# PDD.net
KiCad netlist of a schematic drawn in EAGLE
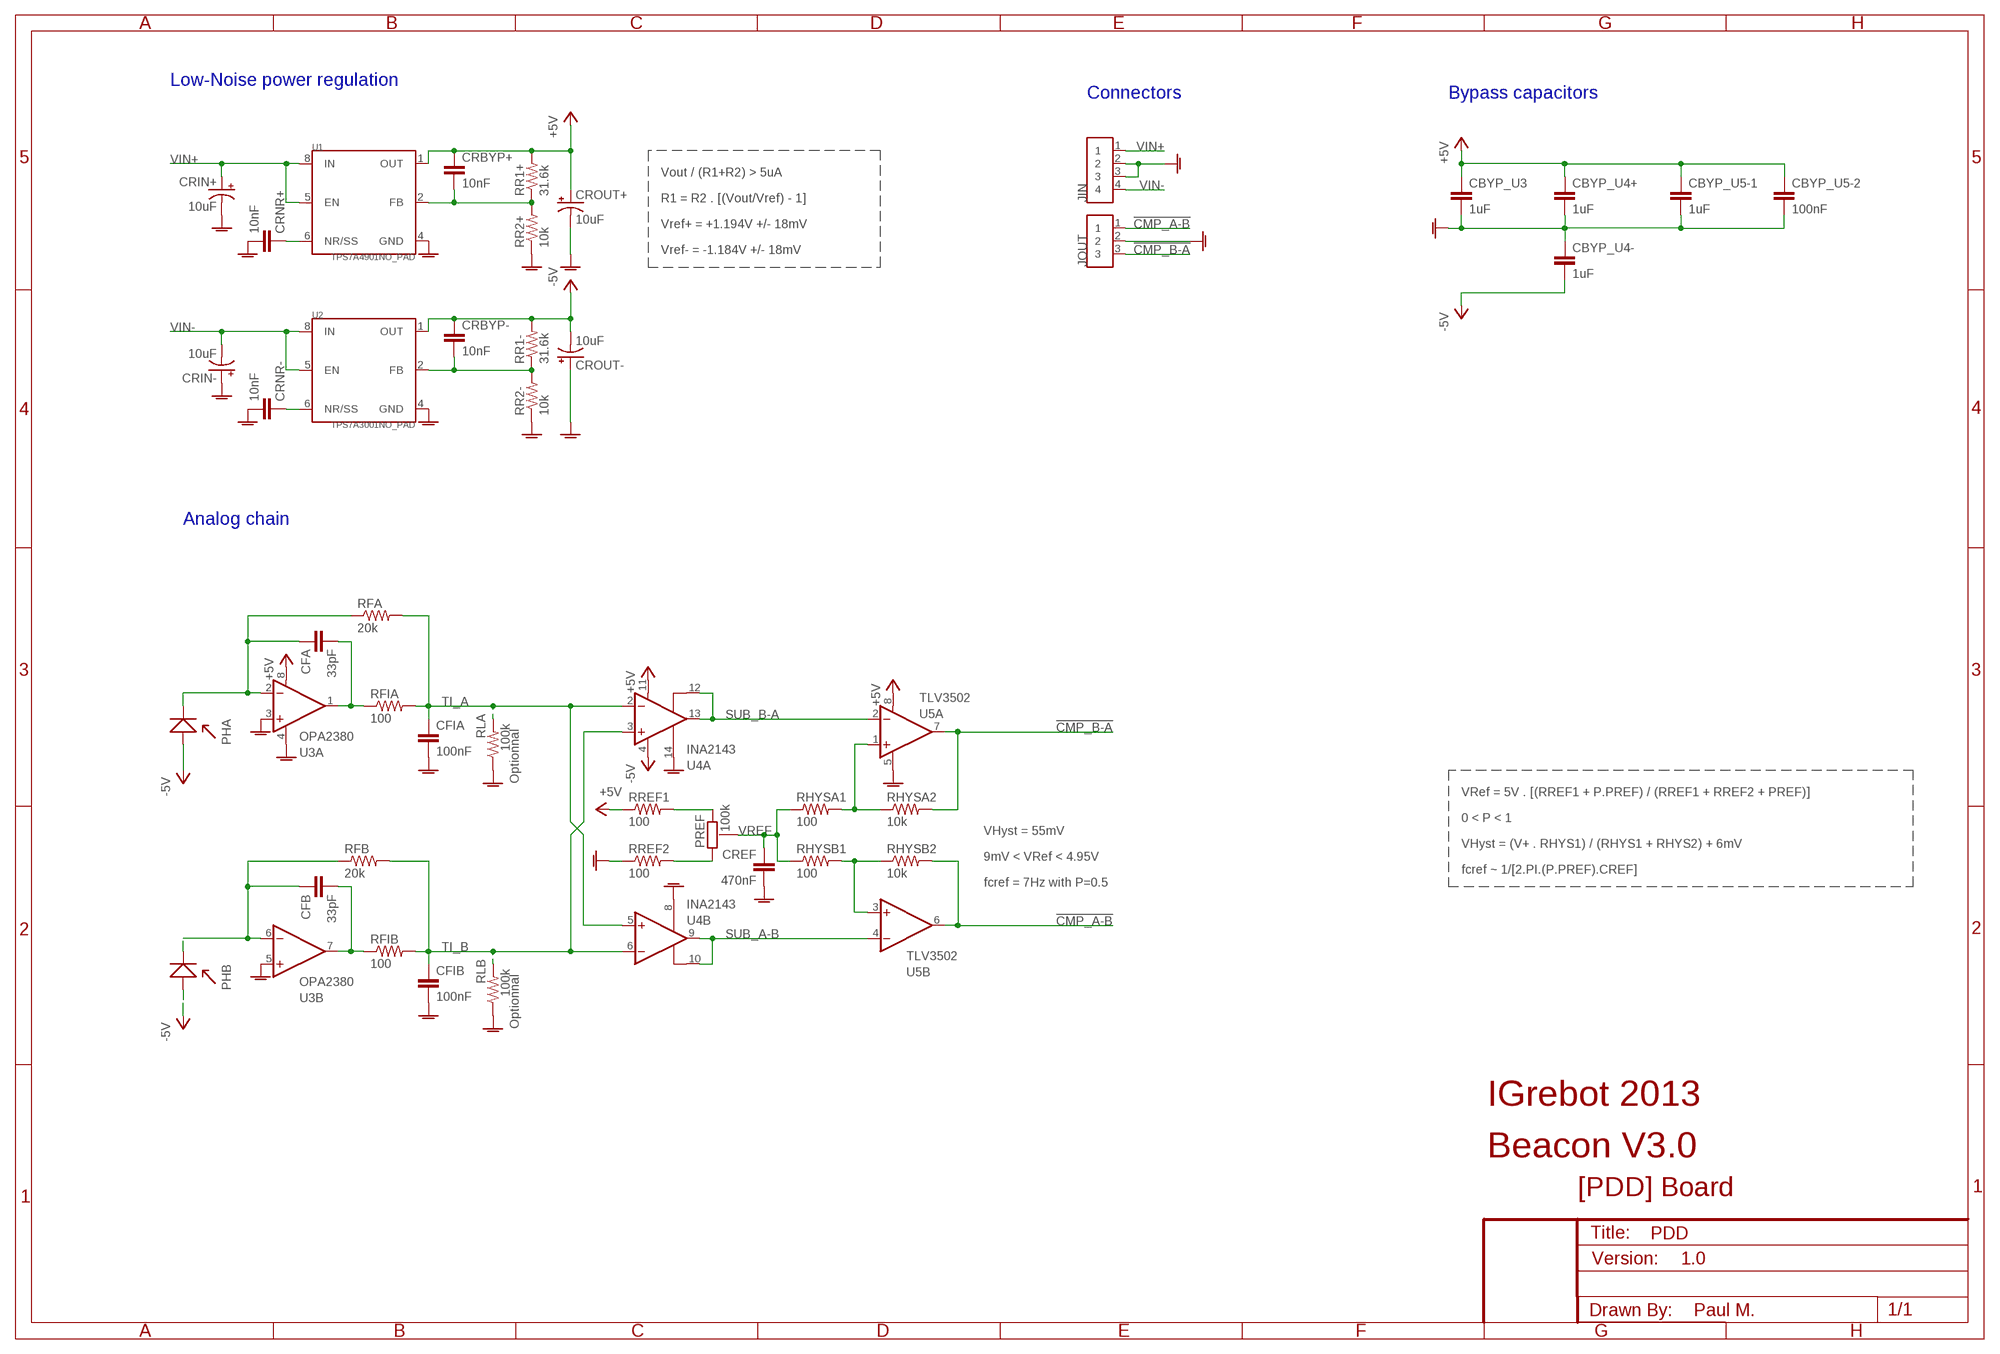
[diagram p0: schematic, sheet 1]

(export (version "E")
  (design (tool "Eeschema 10.0.6"))
  (components
    (comp (ref "CBYP_U3")
      (value "1uF")
      (footprint "eagle-import:0603-CAP")
      (libsource (lib "eagle-import") (part "CAP0603-CAP"))
    )
    (comp (ref "CBYP_U4+")
      (value "1uF")
      (footprint "eagle-import:0603-CAP")
      (libsource (lib "eagle-import") (part "CAP0603-CAP"))
    )
    (comp (ref "CBYP_U4-")
      (value "1uF")
      (footprint "eagle-import:0603-CAP")
      (libsource (lib "eagle-import") (part "CAP0603-CAP"))
    )
    (comp (ref "CBYP_U5-1")
      (value "1uF")
      (footprint "eagle-import:0603-CAP")
      (libsource (lib "eagle-import") (part "CAP0603-CAP"))
    )
    (comp (ref "CBYP_U5-2")
      (value "100nF")
      (footprint "eagle-import:0603-CAP")
      (libsource (lib "eagle-import") (part "CAP0603-CAP"))
    )
    (comp (ref "CFA")
      (value "33pF")
      (footprint "eagle-import:0603-CAP")
      (libsource (lib "eagle-import") (part "CAP0603-CAP"))
    )
    (comp (ref "CFB")
      (value "33pF")
      (footprint "eagle-import:0603-CAP")
      (libsource (lib "eagle-import") (part "CAP0603-CAP"))
    )
    (comp (ref "CFIA")
      (value "100nF")
      (footprint "eagle-import:0603-CAP")
      (libsource (lib "eagle-import") (part "CAP0603-CAP"))
    )
    (comp (ref "CFIB")
      (value "100nF")
      (footprint "eagle-import:0603-CAP")
      (libsource (lib "eagle-import") (part "CAP0603-CAP"))
    )
    (comp (ref "CRBYP+")
      (value "10nF")
      (footprint "eagle-import:0603-CAP")
      (libsource (lib "eagle-import") (part "CAP0603-CAP"))
    )
    (comp (ref "CRBYP-")
      (value "10nF")
      (footprint "eagle-import:0603-CAP")
      (libsource (lib "eagle-import") (part "CAP0603-CAP"))
    )
    (comp (ref "CREF")
      (value "470nF")
      (footprint "eagle-import:0603-CAP")
      (libsource (lib "eagle-import") (part "CAP0603-CAP"))
    )
    (comp (ref "CRIN+")
      (value "10uF")
      (footprint "eagle-import:EIA3528-KIT")
      (libsource (lib "eagle-import") (part "CAP_POL3528-KIT"))
    )
    (comp (ref "CRIN-")
      (value "10uF")
      (footprint "eagle-import:EIA3528-KIT")
      (libsource (lib "eagle-import") (part "CAP_POL3528-KIT"))
    )
    (comp (ref "CRNR+")
      (value "10nF")
      (footprint "eagle-import:0603-CAP")
      (libsource (lib "eagle-import") (part "CAP0603-CAP"))
    )
    (comp (ref "CRNR-")
      (value "10nF")
      (footprint "eagle-import:0603-CAP")
      (libsource (lib "eagle-import") (part "CAP0603-CAP"))
    )
    (comp (ref "CROUT+")
      (value "10uF")
      (footprint "eagle-import:EIA3528-KIT")
      (libsource (lib "eagle-import") (part "CAP_POL3528-KIT"))
    )
    (comp (ref "CROUT-")
      (value "10uF")
      (footprint "eagle-import:EIA3528-KIT")
      (libsource (lib "eagle-import") (part "CAP_POL3528-KIT"))
    )
    (comp (ref "JIN")
      (value "SIL4")
      (footprint "eagle-import:CON4-2.54")
      (libsource (lib "eagle-import") (part "SIL4"))
    )
    (comp (ref "JOUT")
      (value "SIL3")
      (footprint "eagle-import:CON3-2.54")
      (libsource (lib "eagle-import") (part "SIL3"))
    )
    (comp (ref "PHA")
      (value "VBPW34SR")
      (footprint "eagle-import:VBPW34SR")
      (libsource (lib "eagle-import") (part "VBPW34SR"))
    )
    (comp (ref "PHB")
      (value "VBPW34SR")
      (footprint "eagle-import:VBPW34SR")
      (libsource (lib "eagle-import") (part "VBPW34SR"))
    )
    (comp (ref "PREF")
      (value "100k")
      (footprint "eagle-import:TRIM-PVZ2A")
      (libsource (lib "eagle-import") (part "PVZ2A"))
    )
    (comp (ref "RFA")
      (value "20k")
      (footprint "eagle-import:0603-RES")
      (libsource (lib "eagle-import") (part "RESISTOR0603-RES"))
    )
    (comp (ref "RFB")
      (value "20k")
      (footprint "eagle-import:0603-RES")
      (libsource (lib "eagle-import") (part "RESISTOR0603-RES"))
    )
    (comp (ref "RFIA")
      (value "100")
      (footprint "eagle-import:0603-RES")
      (libsource (lib "eagle-import") (part "RESISTOR0603-RES"))
    )
    (comp (ref "RFIB")
      (value "100")
      (footprint "eagle-import:0603-RES")
      (libsource (lib "eagle-import") (part "RESISTOR0603-RES"))
    )
    (comp (ref "RHYSA1")
      (value "100")
      (footprint "eagle-import:0603-RES")
      (libsource (lib "eagle-import") (part "RESISTOR0603-RES"))
    )
    (comp (ref "RHYSA2")
      (value "10k")
      (footprint "eagle-import:0603-RES")
      (libsource (lib "eagle-import") (part "RESISTOR0603-RES"))
    )
    (comp (ref "RHYSB1")
      (value "100")
      (footprint "eagle-import:0603-RES")
      (libsource (lib "eagle-import") (part "RESISTOR0603-RES"))
    )
    (comp (ref "RHYSB2")
      (value "10k")
      (footprint "eagle-import:0603-RES")
      (libsource (lib "eagle-import") (part "RESISTOR0603-RES"))
    )
    (comp (ref "RLA")
      (value "100k")
      (footprint "eagle-import:0603-RES")
      (libsource (lib "eagle-import") (part "RESISTOR0603-RES"))
    )
    (comp (ref "RLB")
      (value "100k")
      (footprint "eagle-import:0603-RES")
      (libsource (lib "eagle-import") (part "RESISTOR0603-RES"))
    )
    (comp (ref "RR1+")
      (value "31.6k")
      (footprint "eagle-import:0603-RES")
      (libsource (lib "eagle-import") (part "RESISTOR0603-RES"))
    )
    (comp (ref "RR1-")
      (value "31.6k")
      (footprint "eagle-import:0603-RES")
      (libsource (lib "eagle-import") (part "RESISTOR0603-RES"))
    )
    (comp (ref "RR2+")
      (value "10k")
      (footprint "eagle-import:0603-RES")
      (libsource (lib "eagle-import") (part "RESISTOR0603-RES"))
    )
    (comp (ref "RR2-")
      (value "10k")
      (footprint "eagle-import:0603-RES")
      (libsource (lib "eagle-import") (part "RESISTOR0603-RES"))
    )
    (comp (ref "RREF1")
      (value "100")
      (footprint "eagle-import:0603-RES")
      (libsource (lib "eagle-import") (part "RESISTOR0603-RES"))
    )
    (comp (ref "RREF2")
      (value "100")
      (footprint "eagle-import:0603-RES")
      (libsource (lib "eagle-import") (part "RESISTOR0603-RES"))
    )
    (comp (ref "U1")
      (value "TPS7A4901NO_PAD")
      (footprint "eagle-import:MSOP8")
      (libsource (lib "eagle-import") (part "TPS7A4901NO_PAD"))
    )
    (comp (ref "U2")
      (value "TPS7A3001NO_PAD")
      (footprint "eagle-import:MSOP8")
      (libsource (lib "eagle-import") (part "TPS7A3001NO_PAD"))
    )
    (comp (ref "U3")
      (value "OPA2380")
      (footprint "eagle-import:MSOP8")
      (libsource (lib "eagle-import") (part "OPA2380"))
    )
    (comp (ref "U4")
      (value "INA2143")
      (footprint "eagle-import:SOIC14")
      (libsource (lib "eagle-import") (part "INA2143"))
    )
    (comp (ref "U5")
      (value "TLV3502")
      (footprint "eagle-import:SOIC8")
      (libsource (lib "eagle-import") (part "TLV3502"))
    )
  )
  (nets
    (net (code "1") (name "+5V") (class "Default")
      (node (ref "CBYP_U3") (pin "1") (pinfunction "1_1") (pintype "passive"))
      (node (ref "CBYP_U4+") (pin "1") (pinfunction "1_1") (pintype "passive"))
      (node (ref "CBYP_U5-1") (pin "1") (pinfunction "1_1") (pintype "passive"))
      (node (ref "CBYP_U5-2") (pin "1") (pinfunction "1_1") (pintype "passive"))
      (node (ref "CRBYP+") (pin "1") (pinfunction "1_1") (pintype "passive"))
      (node (ref "CROUT+") (pin "A") (pinfunction "+_A") (pintype "passive"))
      (node (ref "RR1+") (pin "2") (pinfunction "2_2") (pintype "passive"))
      (node (ref "RREF1") (pin "1") (pinfunction "1_1") (pintype "passive"))
      (node (ref "U1") (pin "1") (pinfunction "OUT_1") (pintype "power_in"))
      (node (ref "U3") (pin "8") (pinfunction "V+_8") (pintype "power_in"))
      (node (ref "U4") (pin "11") (pinfunction "V+_11") (pintype "power_in"))
      (node (ref "U5") (pin "8") (pinfunction "V+_8") (pintype "power_in"))
    )
    (net (code "2") (name "-5V") (class "Default")
      (node (ref "CBYP_U4-") (pin "2") (pinfunction "2_2") (pintype "passive"))
      (node (ref "CRBYP-") (pin "1") (pinfunction "1_1") (pintype "passive"))
      (node (ref "CROUT-") (pin "C") (pinfunction "-_C") (pintype "passive"))
      (node (ref "PHA") (pin "A") (pinfunction "A_A") (pintype "bidirectional"))
      (node (ref "PHB") (pin "A") (pinfunction "A_A") (pintype "bidirectional"))
      (node (ref "RR1-") (pin "2") (pinfunction "2_2") (pintype "passive"))
      (node (ref "U2") (pin "1") (pinfunction "OUT_1") (pintype "power_in"))
      (node (ref "U4") (pin "4") (pinfunction "V-_4") (pintype "power_in"))
    )
    (net (code "3") (name "/SUB_A-B") (class "Default")
      (node (ref "U4") (pin "10") (pinfunction "SENSE_10") (pintype "bidirectional"))
      (node (ref "U4") (pin "9") (pinfunction "OUT_9") (pintype "output"))
      (node (ref "U5") (pin "4") (pinfunction "-IN_4") (pintype "input"))
    )
    (net (code "4") (name "/SUB_B-A") (class "Default")
      (node (ref "U4") (pin "12") (pinfunction "SENSE_12") (pintype "bidirectional"))
      (node (ref "U4") (pin "13") (pinfunction "OUT_13") (pintype "output"))
      (node (ref "U5") (pin "2") (pinfunction "-IN_2") (pintype "input"))
    )
    (net (code "5") (name "/TI_A") (class "Default")
      (node (ref "CFIA") (pin "1") (pinfunction "1_1") (pintype "passive"))
      (node (ref "RFA") (pin "2") (pinfunction "2_2") (pintype "passive"))
      (node (ref "RFIA") (pin "2") (pinfunction "2_2") (pintype "passive"))
      (node (ref "RLA") (pin "2") (pinfunction "2_2") (pintype "passive"))
      (node (ref "U4") (pin "2") (pinfunction "-IN_2") (pintype "input"))
      (node (ref "U4") (pin "5") (pinfunction "+IN_5") (pintype "input"))
    )
    (net (code "6") (name "/TI_B") (class "Default")
      (node (ref "CFIB") (pin "1") (pinfunction "1_1") (pintype "passive"))
      (node (ref "RFB") (pin "2") (pinfunction "2_2") (pintype "passive"))
      (node (ref "RFIB") (pin "2") (pinfunction "2_2") (pintype "passive"))
      (node (ref "RLB") (pin "2") (pinfunction "2_2") (pintype "passive"))
      (node (ref "U4") (pin "3") (pinfunction "+IN_3") (pintype "input"))
      (node (ref "U4") (pin "6") (pinfunction "-IN_6") (pintype "input"))
    )
    (net (code "7") (name "/VIN+") (class "Default")
      (node (ref "CRIN+") (pin "A") (pinfunction "+_A") (pintype "passive"))
      (node (ref "JIN") (pin "1") (pinfunction "1_1") (pintype "bidirectional"))
      (node (ref "U1") (pin "5") (pinfunction "EN_5") (pintype "input"))
      (node (ref "U1") (pin "8") (pinfunction "IN_8") (pintype "power_in"))
    )
    (net (code "8") (name "/VIN-") (class "Default")
      (node (ref "CRIN-") (pin "C") (pinfunction "-_C") (pintype "passive"))
      (node (ref "JIN") (pin "4") (pinfunction "4_4") (pintype "bidirectional"))
      (node (ref "U2") (pin "5") (pinfunction "EN_5") (pintype "input"))
      (node (ref "U2") (pin "8") (pinfunction "IN_8") (pintype "power_in"))
    )
    (net (code "9") (name "/VREF") (class "Default")
      (node (ref "CREF") (pin "1") (pinfunction "1_1") (pintype "passive"))
      (node (ref "PREF") (pin "2") (pinfunction "B_2") (pintype "bidirectional"))
      (node (ref "RHYSA1") (pin "1") (pinfunction "1_1") (pintype "passive"))
      (node (ref "RHYSB1") (pin "1") (pinfunction "1_1") (pintype "passive"))
    )
    (net (code "10") (name "/~{CMP_A-B}") (class "Default")
      (node (ref "JOUT") (pin "1") (pinfunction "1_1") (pintype "bidirectional"))
      (node (ref "RHYSB2") (pin "2") (pinfunction "2_2") (pintype "passive"))
      (node (ref "U5") (pin "6") (pinfunction "OUT_6") (pintype "output"))
    )
    (net (code "11") (name "/~{CMP_B-A}") (class "Default")
      (node (ref "JOUT") (pin "3") (pinfunction "3_3") (pintype "bidirectional"))
      (node (ref "RHYSA2") (pin "2") (pinfunction "2_2") (pintype "passive"))
      (node (ref "U5") (pin "7") (pinfunction "OUT_7") (pintype "output"))
    )
    (net (code "12") (name "AGND") (class "Default")
      (node (ref "CBYP_U3") (pin "2") (pinfunction "2_2") (pintype "passive"))
      (node (ref "CBYP_U4+") (pin "2") (pinfunction "2_2") (pintype "passive"))
      (node (ref "CBYP_U4-") (pin "1") (pinfunction "1_1") (pintype "passive"))
      (node (ref "CBYP_U5-1") (pin "2") (pinfunction "2_2") (pintype "passive"))
      (node (ref "CBYP_U5-2") (pin "2") (pinfunction "2_2") (pintype "passive"))
      (node (ref "CFIA") (pin "2") (pinfunction "2_2") (pintype "passive"))
      (node (ref "CFIB") (pin "2") (pinfunction "2_2") (pintype "passive"))
      (node (ref "CREF") (pin "2") (pinfunction "2_2") (pintype "passive"))
      (node (ref "CRIN+") (pin "C") (pinfunction "-_C") (pintype "passive"))
      (node (ref "CRIN-") (pin "A") (pinfunction "+_A") (pintype "passive"))
      (node (ref "CRNR+") (pin "2") (pinfunction "2_2") (pintype "passive"))
      (node (ref "CRNR-") (pin "2") (pinfunction "2_2") (pintype "passive"))
      (node (ref "CROUT+") (pin "C") (pinfunction "-_C") (pintype "passive"))
      (node (ref "CROUT-") (pin "A") (pinfunction "+_A") (pintype "passive"))
      (node (ref "JIN") (pin "2") (pinfunction "2_2") (pintype "bidirectional"))
      (node (ref "JIN") (pin "3") (pinfunction "3_3") (pintype "bidirectional"))
      (node (ref "JOUT") (pin "2") (pinfunction "2_2") (pintype "bidirectional"))
      (node (ref "RLA") (pin "1") (pinfunction "1_1") (pintype "passive"))
      (node (ref "RLB") (pin "1") (pinfunction "1_1") (pintype "passive"))
      (node (ref "RR2+") (pin "1") (pinfunction "1_1") (pintype "passive"))
      (node (ref "RR2-") (pin "1") (pinfunction "1_1") (pintype "passive"))
      (node (ref "RREF2") (pin "1") (pinfunction "1_1") (pintype "passive"))
      (node (ref "U1") (pin "4") (pinfunction "GND_4") (pintype "power_in"))
      (node (ref "U2") (pin "4") (pinfunction "GND_4") (pintype "power_in"))
      (node (ref "U3") (pin "3") (pinfunction "+IN_3") (pintype "input"))
      (node (ref "U3") (pin "4") (pinfunction "V-_4") (pintype "power_in"))
      (node (ref "U3") (pin "5") (pinfunction "+IN_5") (pintype "input"))
      (node (ref "U4") (pin "14") (pinfunction "REF_14") (pintype "input"))
      (node (ref "U4") (pin "8") (pinfunction "REF_8") (pintype "input"))
      (node (ref "U5") (pin "5") (pinfunction "V-_5") (pintype "power_in"))
    )
    (net (code "13") (name "Net-(PREF-A)") (class "Default")
      (node (ref "PREF") (pin "1") (pinfunction "A_1") (pintype "bidirectional"))
      (node (ref "RREF1") (pin "2") (pinfunction "2_2") (pintype "passive"))
    )
    (net (code "14") (name "Net-(PREF-C)") (class "Default")
      (node (ref "PREF") (pin "3") (pinfunction "C_3") (pintype "bidirectional"))
      (node (ref "RREF2") (pin "2") (pinfunction "2_2") (pintype "passive"))
    )
    (net (code "15") (name "Net-(U1-FB)") (class "Default")
      (node (ref "CRBYP+") (pin "2") (pinfunction "2_2") (pintype "passive"))
      (node (ref "RR1+") (pin "1") (pinfunction "1_1") (pintype "passive"))
      (node (ref "RR2+") (pin "2") (pinfunction "2_2") (pintype "passive"))
      (node (ref "U1") (pin "2") (pinfunction "FB_2") (pintype "bidirectional"))
    )
    (net (code "16") (name "Net-(U1-NR{slash}SS)") (class "Default")
      (node (ref "CRNR+") (pin "1") (pinfunction "1_1") (pintype "passive"))
      (node (ref "U1") (pin "6") (pinfunction "NR/SS_6") (pintype "input"))
    )
    (net (code "17") (name "Net-(U2-FB)") (class "Default")
      (node (ref "CRBYP-") (pin "2") (pinfunction "2_2") (pintype "passive"))
      (node (ref "RR1-") (pin "1") (pinfunction "1_1") (pintype "passive"))
      (node (ref "RR2-") (pin "2") (pinfunction "2_2") (pintype "passive"))
      (node (ref "U2") (pin "2") (pinfunction "FB_2") (pintype "bidirectional"))
    )
    (net (code "18") (name "Net-(U2-NR{slash}SS)") (class "Default")
      (node (ref "CRNR-") (pin "1") (pinfunction "1_1") (pintype "passive"))
      (node (ref "U2") (pin "6") (pinfunction "NR/SS_6") (pintype "input"))
    )
    (net (code "19") (name "Net-(U3A--IN)") (class "Default")
      (node (ref "CFA") (pin "1") (pinfunction "1_1") (pintype "passive"))
      (node (ref "PHA") (pin "K") (pinfunction "K_K") (pintype "bidirectional"))
      (node (ref "RFA") (pin "1") (pinfunction "1_1") (pintype "passive"))
      (node (ref "U3") (pin "2") (pinfunction "-IN_2") (pintype "input"))
    )
    (net (code "20") (name "Net-(U3A-OUT)") (class "Default")
      (node (ref "CFA") (pin "2") (pinfunction "2_2") (pintype "passive"))
      (node (ref "RFIA") (pin "1") (pinfunction "1_1") (pintype "passive"))
      (node (ref "U3") (pin "1") (pinfunction "OUT_1") (pintype "output"))
    )
    (net (code "21") (name "Net-(U3B--IN)") (class "Default")
      (node (ref "CFB") (pin "1") (pinfunction "1_1") (pintype "passive"))
      (node (ref "PHB") (pin "K") (pinfunction "K_K") (pintype "bidirectional"))
      (node (ref "RFB") (pin "1") (pinfunction "1_1") (pintype "passive"))
      (node (ref "U3") (pin "6") (pinfunction "-IN_6") (pintype "input"))
    )
    (net (code "22") (name "Net-(U3B-OUT)") (class "Default")
      (node (ref "CFB") (pin "2") (pinfunction "2_2") (pintype "passive"))
      (node (ref "RFIB") (pin "1") (pinfunction "1_1") (pintype "passive"))
      (node (ref "U3") (pin "7") (pinfunction "OUT_7") (pintype "output"))
    )
    (net (code "23") (name "Net-(U5A-+IN)") (class "Default")
      (node (ref "RHYSA1") (pin "2") (pinfunction "2_2") (pintype "passive"))
      (node (ref "RHYSA2") (pin "1") (pinfunction "1_1") (pintype "passive"))
      (node (ref "U5") (pin "1") (pinfunction "+IN_1") (pintype "input"))
    )
    (net (code "24") (name "Net-(U5B-+IN)") (class "Default")
      (node (ref "RHYSB1") (pin "2") (pinfunction "2_2") (pintype "passive"))
      (node (ref "RHYSB2") (pin "1") (pinfunction "1_1") (pintype "passive"))
      (node (ref "U5") (pin "3") (pinfunction "+IN_3") (pintype "input"))
    )
  )
)
